# Underwater_ROV_RPI.net
KiCad netlist of a schematic drawn in Altium Designer
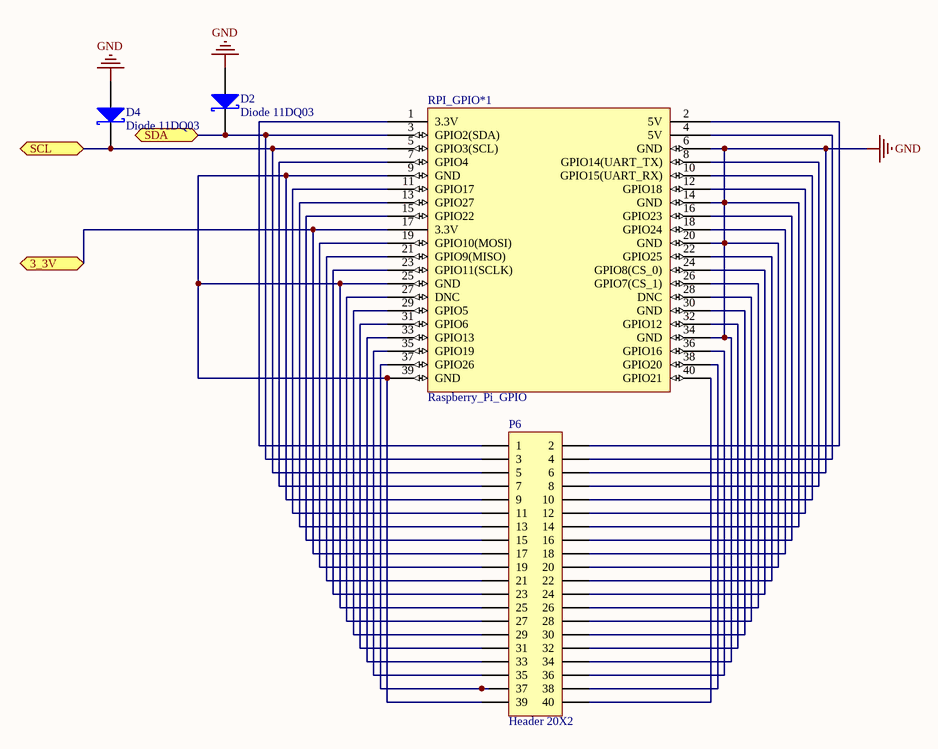
[diagram p0: Underwater_ROV_RPI.SchDoc]

(export (version "E")
  (design (tool "Eeschema 10.0.6"))
  (components
    (comp (ref "D2")
      (value "Diode 11DQ03")
      (footprint "DO-204AL")
      (description "Schottky Rectifier")
      (fields (field (name "PUBLISHER") "Altium Limited"))
      (libsource (lib "Miscellaneous Devices") (part "Diode 11DQ03"))
    )
    (comp (ref "D4")
      (value "Diode 11DQ03")
      (footprint "DO-204AL")
      (description "Schottky Rectifier")
      (fields (field (name "PUBLISHER") "Altium Limited"))
      (libsource (lib "Miscellaneous Devices") (part "Diode 11DQ03"))
    )
    (comp (ref "P6")
      (value "Header 20X2")
      (footprint "HDR2X20")
      (description "Header, 20-Pin, Dual row")
      (fields (field (name "PUBLISHER") "Altium Limited"))
      (libsource (lib "Miscellaneous Connectors") (part "Header 20X2"))
    )
    (comp (ref "RPI_GPIO*1")
      (value "Raspberry_Pi_GPIO")
      (footprint "HDR2X20")
      (libsource (lib "UROV_Aux_Lib") (part "Raspberry_Pi_GPIO"))
    )
  )
  (nets
    (net (code "1") (name "/3_3V") (class "Default")
      (node (ref "P6") (pin "17") (pinfunction "17_17") (pintype "passive"))
      (node (ref "RPI_GPIO*1") (pin "17") (pinfunction "3.3V_17") (pintype "power_in"))
    )
    (net (code "2") (name "/SCL") (class "Default")
      (node (ref "D4") (pin "2") (pinfunction "K_2") (pintype "passive"))
      (node (ref "P6") (pin "5") (pinfunction "5_5") (pintype "passive"))
      (node (ref "RPI_GPIO*1") (pin "5") (pinfunction "GPIO3(SCL)_5") (pintype "bidirectional"))
    )
    (net (code "3") (name "/SDA") (class "Default")
      (node (ref "D2") (pin "2") (pinfunction "K_2") (pintype "passive"))
      (node (ref "P6") (pin "3") (pinfunction "3_3") (pintype "passive"))
      (node (ref "RPI_GPIO*1") (pin "3") (pinfunction "GPIO2(SDA)_3") (pintype "bidirectional"))
    )
    (net (code "4") (name "GND") (class "Default")
      (node (ref "D2") (pin "1") (pinfunction "A_1") (pintype "passive"))
      (node (ref "D4") (pin "1") (pinfunction "A_1") (pintype "passive"))
      (node (ref "P6") (pin "14") (pinfunction "14_14") (pintype "passive"))
      (node (ref "P6") (pin "20") (pinfunction "20_20") (pintype "passive"))
      (node (ref "P6") (pin "34") (pinfunction "34_34") (pintype "passive"))
      (node (ref "P6") (pin "6") (pinfunction "6_6") (pintype "passive"))
      (node (ref "RPI_GPIO*1") (pin "14") (pinfunction "GND_14") (pintype "bidirectional"))
      (node (ref "RPI_GPIO*1") (pin "20") (pinfunction "GND_20") (pintype "bidirectional"))
      (node (ref "RPI_GPIO*1") (pin "34") (pinfunction "GND_34") (pintype "bidirectional"))
      (node (ref "RPI_GPIO*1") (pin "6") (pinfunction "GND_6") (pintype "bidirectional"))
    )
    (net (code "5") (name "Net-(P6-Pad1)") (class "Default")
      (node (ref "P6") (pin "1") (pinfunction "1_1") (pintype "passive"))
      (node (ref "RPI_GPIO*1") (pin "1") (pinfunction "3.3V_1") (pintype "power_in"))
    )
    (net (code "6") (name "Net-(P6-Pad2)") (class "Default")
      (node (ref "P6") (pin "2") (pinfunction "2_2") (pintype "passive"))
      (node (ref "RPI_GPIO*1") (pin "2") (pinfunction "5V_2") (pintype "power_in"))
    )
    (net (code "7") (name "Net-(P6-Pad4)") (class "Default")
      (node (ref "P6") (pin "4") (pinfunction "4_4") (pintype "passive"))
      (node (ref "RPI_GPIO*1") (pin "4") (pinfunction "5V_4") (pintype "power_in"))
    )
    (net (code "8") (name "Net-(P6-Pad25)") (class "Default")
      (node (ref "P6") (pin "25") (pinfunction "25_25") (pintype "passive"))
      (node (ref "P6") (pin "39") (pinfunction "39_39") (pintype "passive"))
      (node (ref "P6") (pin "9") (pinfunction "9_9") (pintype "passive"))
      (node (ref "RPI_GPIO*1") (pin "25") (pinfunction "GND_25") (pintype "bidirectional"))
      (node (ref "RPI_GPIO*1") (pin "39") (pinfunction "GND_39") (pintype "bidirectional"))
      (node (ref "RPI_GPIO*1") (pin "9") (pinfunction "GND_9") (pintype "bidirectional"))
    )
    (net (code "9") (name "Net-(P6-Pad27)") (class "Default")
      (node (ref "P6") (pin "27") (pinfunction "27_27") (pintype "passive"))
      (node (ref "RPI_GPIO*1") (pin "27") (pinfunction "DNC_27") (pintype "bidirectional"))
    )
    (net (code "10") (name "Net-(P6-Pad28)") (class "Default")
      (node (ref "P6") (pin "28") (pinfunction "28_28") (pintype "passive"))
      (node (ref "RPI_GPIO*1") (pin "28") (pinfunction "DNC_28") (pintype "bidirectional"))
    )
    (net (code "11") (name "Net-(P6-Pad30)") (class "Default")
      (node (ref "P6") (pin "30") (pinfunction "30_30") (pintype "passive"))
      (node (ref "RPI_GPIO*1") (pin "30") (pinfunction "GND_30") (pintype "bidirectional"))
    )
    (net (code "12") (name "Net-(RPI_GPIO*1-GPIO4)") (class "Default")
      (node (ref "P6") (pin "7") (pinfunction "7_7") (pintype "passive"))
      (node (ref "RPI_GPIO*1") (pin "7") (pinfunction "GPIO4_7") (pintype "bidirectional"))
    )
    (net (code "13") (name "Net-(RPI_GPIO*1-GPIO5)") (class "Default")
      (node (ref "P6") (pin "29") (pinfunction "29_29") (pintype "passive"))
      (node (ref "RPI_GPIO*1") (pin "29") (pinfunction "GPIO5_29") (pintype "bidirectional"))
    )
    (net (code "14") (name "Net-(RPI_GPIO*1-GPIO6)") (class "Default")
      (node (ref "P6") (pin "31") (pinfunction "31_31") (pintype "passive"))
      (node (ref "RPI_GPIO*1") (pin "31") (pinfunction "GPIO6_31") (pintype "bidirectional"))
    )
    (net (code "15") (name "Net-(RPI_GPIO*1-GPIO7(CS_1))") (class "Default")
      (node (ref "P6") (pin "26") (pinfunction "26_26") (pintype "passive"))
      (node (ref "RPI_GPIO*1") (pin "26") (pinfunction "GPIO7(CS_1)_26") (pintype "bidirectional"))
    )
    (net (code "16") (name "Net-(RPI_GPIO*1-GPIO8(CS_0))") (class "Default")
      (node (ref "P6") (pin "24") (pinfunction "24_24") (pintype "passive"))
      (node (ref "RPI_GPIO*1") (pin "24") (pinfunction "GPIO8(CS_0)_24") (pintype "bidirectional"))
    )
    (net (code "17") (name "Net-(RPI_GPIO*1-GPIO9(MISO))") (class "Default")
      (node (ref "P6") (pin "21") (pinfunction "21_21") (pintype "passive"))
      (node (ref "RPI_GPIO*1") (pin "21") (pinfunction "GPIO9(MISO)_21") (pintype "bidirectional"))
    )
    (net (code "18") (name "Net-(RPI_GPIO*1-GPIO10(MOSI))") (class "Default")
      (node (ref "P6") (pin "19") (pinfunction "19_19") (pintype "passive"))
      (node (ref "RPI_GPIO*1") (pin "19") (pinfunction "GPIO10(MOSI)_19") (pintype "bidirectional"))
    )
    (net (code "19") (name "Net-(RPI_GPIO*1-GPIO11(SCLK))") (class "Default")
      (node (ref "P6") (pin "23") (pinfunction "23_23") (pintype "passive"))
      (node (ref "RPI_GPIO*1") (pin "23") (pinfunction "GPIO11(SCLK)_23") (pintype "bidirectional"))
    )
    (net (code "20") (name "Net-(RPI_GPIO*1-GPIO12)") (class "Default")
      (node (ref "P6") (pin "32") (pinfunction "32_32") (pintype "passive"))
      (node (ref "RPI_GPIO*1") (pin "32") (pinfunction "GPIO12_32") (pintype "bidirectional"))
    )
    (net (code "21") (name "Net-(RPI_GPIO*1-GPIO13)") (class "Default")
      (node (ref "P6") (pin "33") (pinfunction "33_33") (pintype "passive"))
      (node (ref "RPI_GPIO*1") (pin "33") (pinfunction "GPIO13_33") (pintype "bidirectional"))
    )
    (net (code "22") (name "Net-(RPI_GPIO*1-GPIO14(UART_TX))") (class "Default")
      (node (ref "P6") (pin "8") (pinfunction "8_8") (pintype "passive"))
      (node (ref "RPI_GPIO*1") (pin "8") (pinfunction "GPIO14(UART_TX)_8") (pintype "bidirectional"))
    )
    (net (code "23") (name "Net-(RPI_GPIO*1-GPIO15(UART_RX))") (class "Default")
      (node (ref "P6") (pin "10") (pinfunction "10_10") (pintype "passive"))
      (node (ref "RPI_GPIO*1") (pin "10") (pinfunction "GPIO15(UART_RX)_10") (pintype "bidirectional"))
    )
    (net (code "24") (name "Net-(RPI_GPIO*1-GPIO16)") (class "Default")
      (node (ref "P6") (pin "36") (pinfunction "36_36") (pintype "passive"))
      (node (ref "RPI_GPIO*1") (pin "36") (pinfunction "GPIO16_36") (pintype "bidirectional"))
    )
    (net (code "25") (name "Net-(RPI_GPIO*1-GPIO17)") (class "Default")
      (node (ref "P6") (pin "11") (pinfunction "11_11") (pintype "passive"))
      (node (ref "RPI_GPIO*1") (pin "11") (pinfunction "GPIO17_11") (pintype "bidirectional"))
    )
    (net (code "26") (name "Net-(RPI_GPIO*1-GPIO18)") (class "Default")
      (node (ref "P6") (pin "12") (pinfunction "12_12") (pintype "passive"))
      (node (ref "RPI_GPIO*1") (pin "12") (pinfunction "GPIO18_12") (pintype "bidirectional"))
    )
    (net (code "27") (name "Net-(RPI_GPIO*1-GPIO19)") (class "Default")
      (node (ref "P6") (pin "35") (pinfunction "35_35") (pintype "passive"))
      (node (ref "RPI_GPIO*1") (pin "35") (pinfunction "GPIO19_35") (pintype "bidirectional"))
    )
    (net (code "28") (name "Net-(RPI_GPIO*1-GPIO20)") (class "Default")
      (node (ref "P6") (pin "38") (pinfunction "38_38") (pintype "passive"))
      (node (ref "RPI_GPIO*1") (pin "38") (pinfunction "GPIO20_38") (pintype "bidirectional"))
    )
    (net (code "29") (name "Net-(RPI_GPIO*1-GPIO21)") (class "Default")
      (node (ref "P6") (pin "40") (pinfunction "40_40") (pintype "passive"))
      (node (ref "RPI_GPIO*1") (pin "40") (pinfunction "GPIO21_40") (pintype "bidirectional"))
    )
    (net (code "30") (name "Net-(RPI_GPIO*1-GPIO22)") (class "Default")
      (node (ref "P6") (pin "15") (pinfunction "15_15") (pintype "passive"))
      (node (ref "RPI_GPIO*1") (pin "15") (pinfunction "GPIO22_15") (pintype "bidirectional"))
    )
    (net (code "31") (name "Net-(RPI_GPIO*1-GPIO23)") (class "Default")
      (node (ref "P6") (pin "16") (pinfunction "16_16") (pintype "passive"))
      (node (ref "RPI_GPIO*1") (pin "16") (pinfunction "GPIO23_16") (pintype "bidirectional"))
    )
    (net (code "32") (name "Net-(RPI_GPIO*1-GPIO24)") (class "Default")
      (node (ref "P6") (pin "18") (pinfunction "18_18") (pintype "passive"))
      (node (ref "RPI_GPIO*1") (pin "18") (pinfunction "GPIO24_18") (pintype "bidirectional"))
    )
    (net (code "33") (name "Net-(RPI_GPIO*1-GPIO25)") (class "Default")
      (node (ref "P6") (pin "22") (pinfunction "22_22") (pintype "passive"))
      (node (ref "RPI_GPIO*1") (pin "22") (pinfunction "GPIO25_22") (pintype "bidirectional"))
    )
    (net (code "34") (name "Net-(RPI_GPIO*1-GPIO26)") (class "Default")
      (node (ref "P6") (pin "37") (pinfunction "37_37") (pintype "passive"))
      (node (ref "RPI_GPIO*1") (pin "37") (pinfunction "GPIO26_37") (pintype "bidirectional"))
    )
    (net (code "35") (name "Net-(RPI_GPIO*1-GPIO27)") (class "Default")
      (node (ref "P6") (pin "13") (pinfunction "13_13") (pintype "passive"))
      (node (ref "RPI_GPIO*1") (pin "13") (pinfunction "GPIO27_13") (pintype "bidirectional"))
    )
  )
)
